# Servo_Ver_1_2.net
KiCad netlist of a schematic drawn in EAGLE
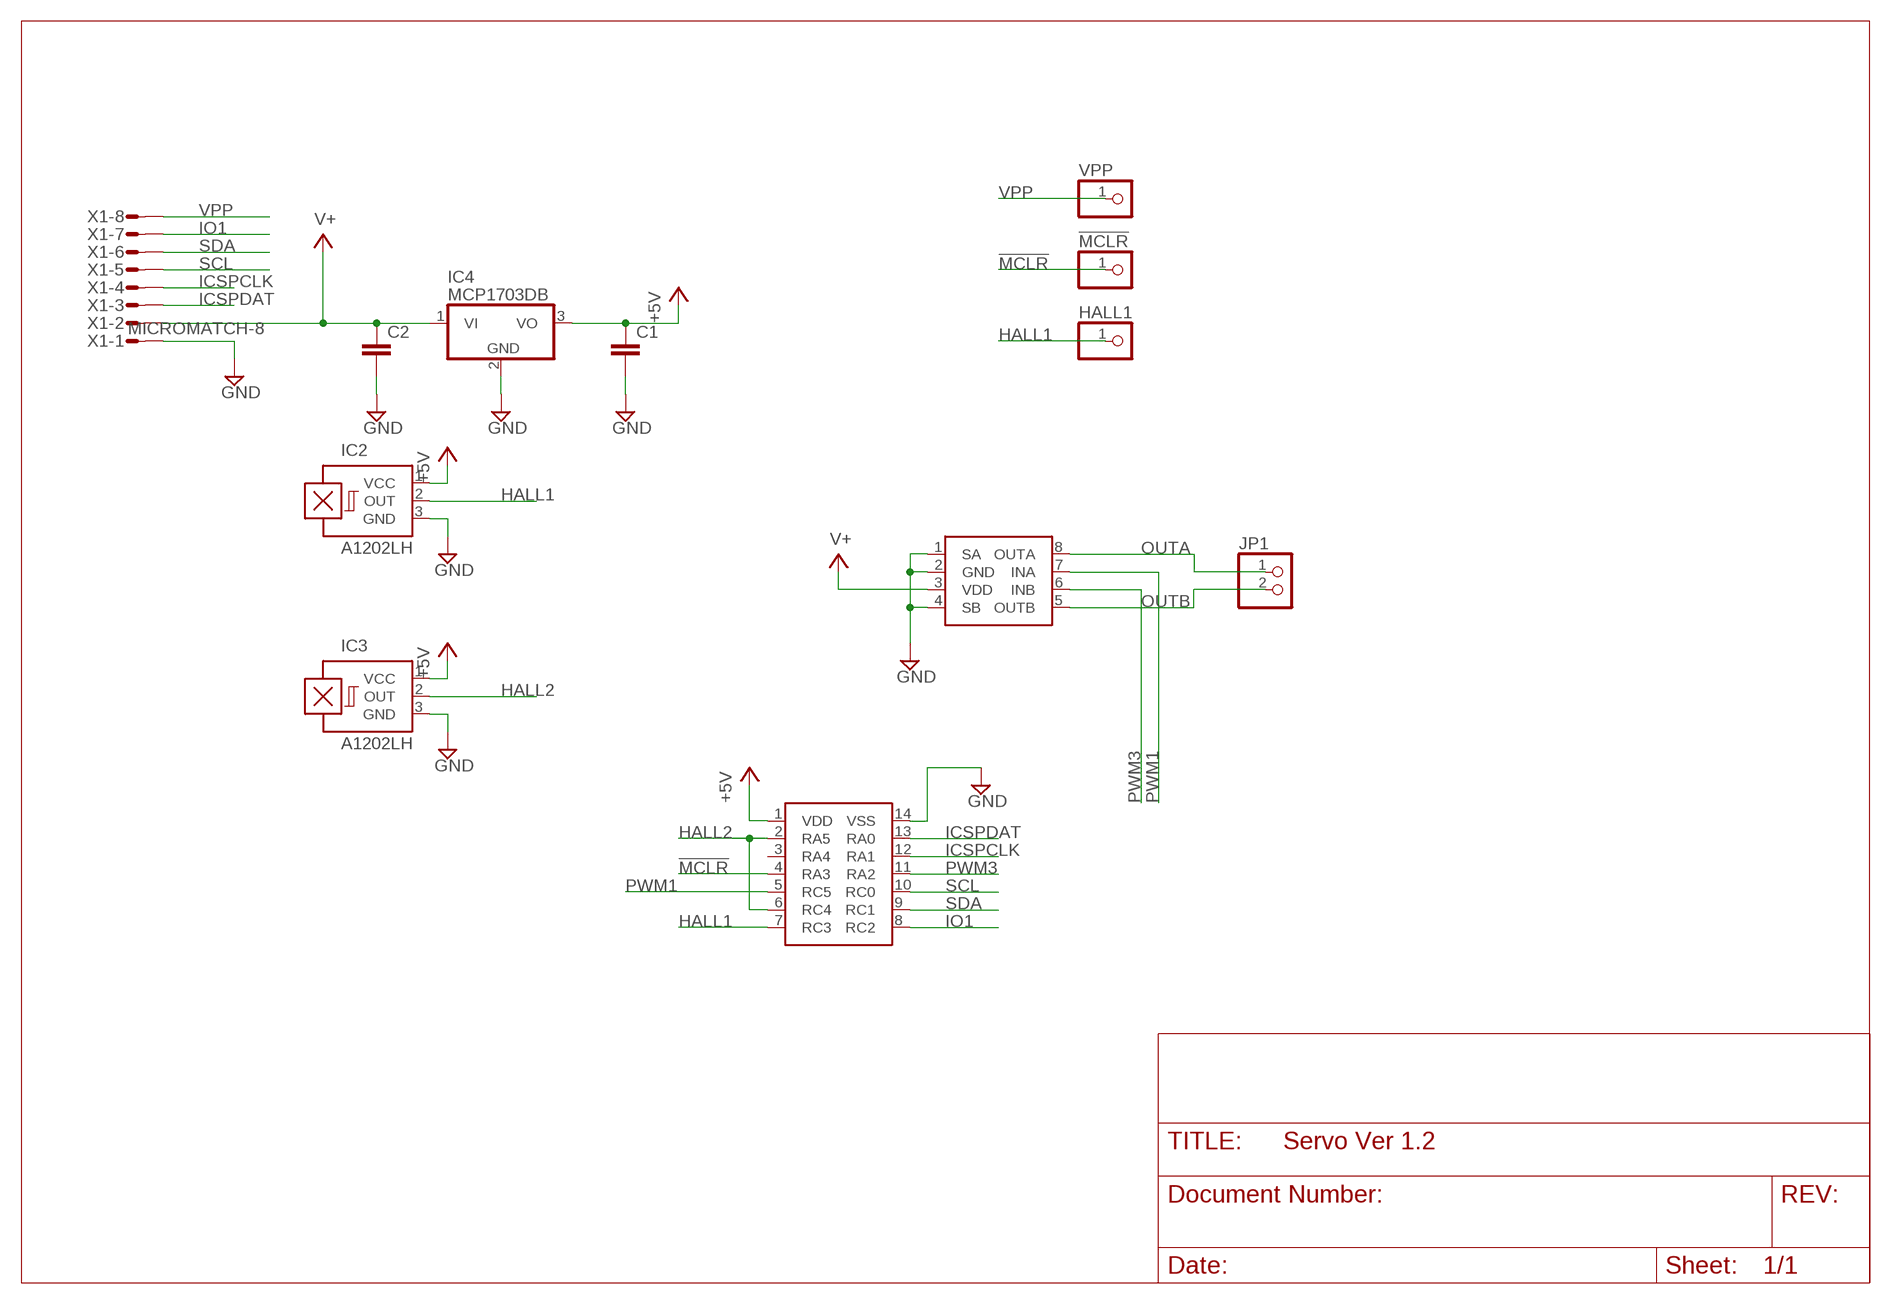
[diagram p0: schematic, sheet 1]

(export (version "E")
  (design (tool "Eeschema 10.0.6"))
  (components
    (comp (ref "!MCLR")
      (value "PINHD-1X1")
      (footprint "eagle-import:1X01")
      (libsource (lib "eagle-import") (part "PINHD-1X1"))
    )
    (comp (ref "C1")
      (value "C-EUC1206")
      (footprint "eagle-import:C1206")
      (libsource (lib "eagle-import") (part "C-EUC1206"))
    )
    (comp (ref "C2")
      (value "C-EUC1206")
      (footprint "eagle-import:C1206")
      (libsource (lib "eagle-import") (part "C-EUC1206"))
    )
    (comp (ref "HALL1")
      (value "PINHD-1X1")
      (footprint "eagle-import:1X01")
      (libsource (lib "eagle-import") (part "PINHD-1X1"))
    )
    (comp (ref "IC2")
      (value "A1202LH")
      (footprint "eagle-import:SOT23-W")
      (libsource (lib "eagle-import") (part "A12?LH02"))
    )
    (comp (ref "IC3")
      (value "A1202LH")
      (footprint "eagle-import:SOT23-W")
      (libsource (lib "eagle-import") (part "A12?LH02"))
    )
    (comp (ref "IC4")
      (value "MCP1703DB")
      (footprint "eagle-import:SOT223")
      (libsource (lib "eagle-import") (part "MCP1703DB"))
    )
    (comp (ref "JP1")
      (value "PINHD-1X2")
      (footprint "eagle-import:1X02")
      (libsource (lib "eagle-import") (part "PINHD-1X2"))
    )
    (comp (ref "U$1")
      (value "PIC16F1503SOIC")
      (footprint "eagle-import:SO-14")
      (libsource (lib "eagle-import") (part "PIC16F1503SOIC"))
    )
    (comp (ref "U$2")
      (value "SI9986SO8")
      (footprint "eagle-import:SO-08")
      (libsource (lib "eagle-import") (part "SI9986SO8"))
    )
    (comp (ref "VPP")
      (value "PINHD-1X1")
      (footprint "eagle-import:1X01")
      (libsource (lib "eagle-import") (part "PINHD-1X1"))
    )
    (comp (ref "X1")
      (value "MICROMATCH-8")
      (footprint "eagle-import:MICROMATCH-8")
      (fields (field (name "MF") "FARNELL") (field (name "MPN") "7-215464-8"))
      (libsource (lib "eagle-import") (part "MICROMATCH-8"))
    )
  )
  (nets
    (net (code "1") (name "+5V") (class "Default")
      (node (ref "C1") (pin "1") (pinfunction "1_1") (pintype "passive"))
      (node (ref "IC2") (pin "1") (pinfunction "VCC_1") (pintype "power_in"))
      (node (ref "IC3") (pin "1") (pinfunction "VCC_1") (pintype "power_in"))
      (node (ref "IC4") (pin "3") (pinfunction "VO_3") (pintype "passive"))
      (node (ref "U$1") (pin "1") (pinfunction "VDD_1") (pintype "power_in"))
    )
    (net (code "2") (name "/HALL1") (class "Default")
      (node (ref "HALL1") (pin "1") (pinfunction "1_1") (pintype "passive"))
      (node (ref "IC2") (pin "2") (pinfunction "OUT_2") (pintype "output"))
      (node (ref "U$1") (pin "7") (pinfunction "RC3_7") (pintype "bidirectional"))
    )
    (net (code "3") (name "/HALL2") (class "Default")
      (node (ref "IC3") (pin "2") (pinfunction "OUT_2") (pintype "output"))
      (node (ref "U$1") (pin "2") (pinfunction "RA5_2") (pintype "bidirectional"))
      (node (ref "U$1") (pin "6") (pinfunction "RC4_6") (pintype "bidirectional"))
    )
    (net (code "4") (name "/ICSPCLK") (class "Default")
      (node (ref "U$1") (pin "12") (pinfunction "RA1_12") (pintype "bidirectional"))
      (node (ref "X1") (pin "4") (pinfunction "S_4") (pintype "passive"))
    )
    (net (code "5") (name "/ICSPDAT") (class "Default")
      (node (ref "U$1") (pin "13") (pinfunction "RA0_13") (pintype "bidirectional"))
      (node (ref "X1") (pin "3") (pinfunction "S_3") (pintype "passive"))
    )
    (net (code "6") (name "/IO1") (class "Default")
      (node (ref "U$1") (pin "8") (pinfunction "RC2_8") (pintype "bidirectional"))
      (node (ref "X1") (pin "7") (pinfunction "S_7") (pintype "passive"))
    )
    (net (code "7") (name "/OUTA") (class "Default")
      (node (ref "JP1") (pin "1") (pinfunction "1_1") (pintype "passive"))
      (node (ref "U$2") (pin "8") (pinfunction "OUTA_8") (pintype "output"))
    )
    (net (code "8") (name "/OUTB") (class "Default")
      (node (ref "JP1") (pin "2") (pinfunction "2_2") (pintype "passive"))
      (node (ref "U$2") (pin "5") (pinfunction "OUTB_5") (pintype "output"))
    )
    (net (code "9") (name "/PWM1") (class "Default")
      (node (ref "U$1") (pin "5") (pinfunction "RC5_5") (pintype "bidirectional"))
      (node (ref "U$2") (pin "7") (pinfunction "INA_7") (pintype "input"))
    )
    (net (code "10") (name "/PWM3") (class "Default")
      (node (ref "U$1") (pin "11") (pinfunction "RA2_11") (pintype "bidirectional"))
      (node (ref "U$2") (pin "6") (pinfunction "INB_6") (pintype "input"))
    )
    (net (code "11") (name "/SCL") (class "Default")
      (node (ref "U$1") (pin "10") (pinfunction "RC0_10") (pintype "bidirectional"))
      (node (ref "X1") (pin "5") (pinfunction "S_5") (pintype "passive"))
    )
    (net (code "12") (name "/SDA") (class "Default")
      (node (ref "U$1") (pin "9") (pinfunction "RC1_9") (pintype "bidirectional"))
      (node (ref "X1") (pin "6") (pinfunction "S_6") (pintype "passive"))
    )
    (net (code "13") (name "/VPP") (class "Default")
      (node (ref "VPP") (pin "1") (pinfunction "1_1") (pintype "passive"))
      (node (ref "X1") (pin "8") (pinfunction "S_8") (pintype "passive"))
    )
    (net (code "14") (name "/~{MCLR}") (class "Default")
      (node (ref "!MCLR") (pin "1") (pinfunction "1_1") (pintype "passive"))
      (node (ref "U$1") (pin "4") (pinfunction "RA3_4") (pintype "input"))
    )
    (net (code "15") (name "GND") (class "Default")
      (node (ref "C1") (pin "2") (pinfunction "2_2") (pintype "passive"))
      (node (ref "C2") (pin "2") (pinfunction "2_2") (pintype "passive"))
      (node (ref "IC2") (pin "3") (pinfunction "GND_3") (pintype "power_in"))
      (node (ref "IC3") (pin "3") (pinfunction "GND_3") (pintype "power_in"))
      (node (ref "IC4") (pin "2") (pinfunction "GND_2") (pintype "passive"))
      (node (ref "U$1") (pin "14") (pinfunction "VSS_14") (pintype "power_in"))
      (node (ref "U$2") (pin "1") (pinfunction "SA_1") (pintype "power_in"))
      (node (ref "U$2") (pin "2") (pinfunction "GND_2") (pintype "power_in"))
      (node (ref "U$2") (pin "4") (pinfunction "SB_4") (pintype "power_in"))
      (node (ref "X1") (pin "1") (pinfunction "S_1") (pintype "passive"))
    )
    (net (code "16") (name "V+") (class "Default")
      (node (ref "C2") (pin "1") (pinfunction "1_1") (pintype "passive"))
      (node (ref "IC4") (pin "1") (pinfunction "VI_1") (pintype "input"))
      (node (ref "U$2") (pin "3") (pinfunction "VDD_3") (pintype "power_in"))
      (node (ref "X1") (pin "2") (pinfunction "S_2") (pintype "passive"))
    )
    (net (code "17") (name "unconnected-(U$1-RA4-Pad3)") (class "Default")
      (node (ref "U$1") (pin "3") (pinfunction "RA4_3") (pintype "bidirectional"))
    )
  )
)
